# gigatron-sn76489.net
KiCad netlist of a schematic drawn in EAGLE
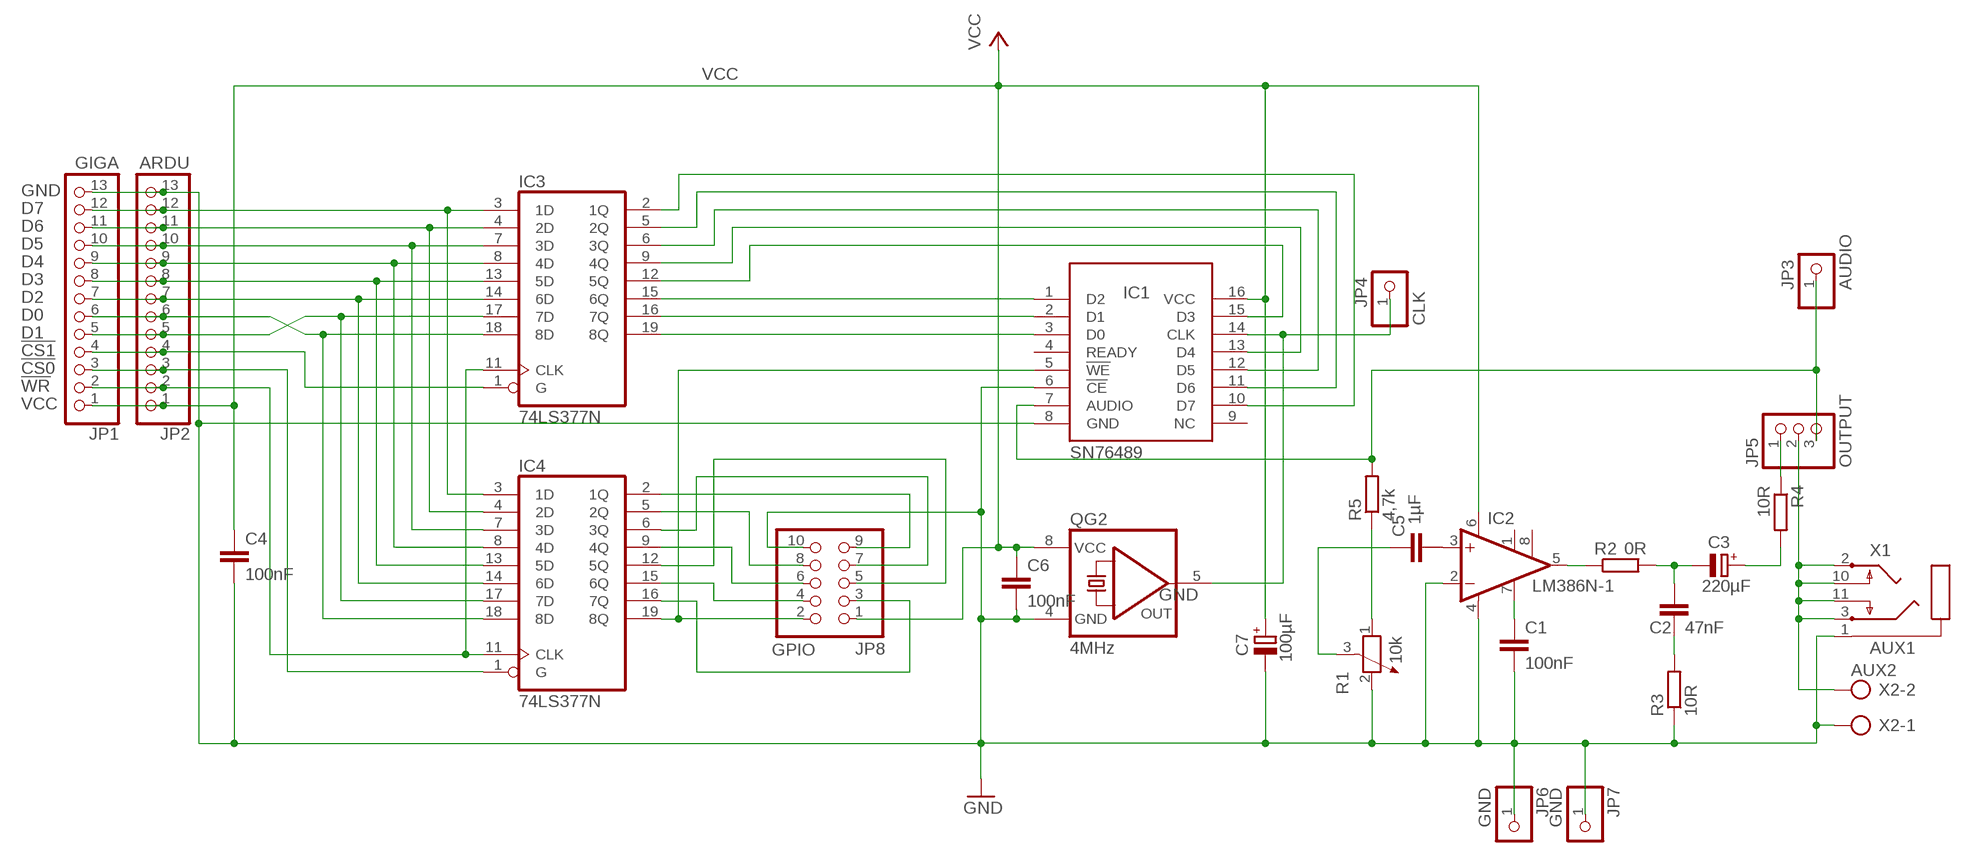
[diagram p0: schematic, sheet 1]

(export (version "E")
  (design (tool "Eeschema 10.0.6"))
  (components
    (comp (ref "C1")
      (value "100nF")
      (footprint "eagle-import:C050-025X075")
      (libsource (lib "eagle-import") (part "C-EU050-025X075"))
    )
    (comp (ref "C2")
      (value "47nF")
      (footprint "eagle-import:C050-025X075")
      (libsource (lib "eagle-import") (part "C-EU050-025X075"))
    )
    (comp (ref "C3")
      (value "220µF")
      (footprint "eagle-import:E2,5-7")
      (libsource (lib "eagle-import") (part "CPOL-EUE2.5-7"))
    )
    (comp (ref "C4")
      (value "100nF")
      (footprint "eagle-import:C050-025X075")
      (libsource (lib "eagle-import") (part "C-EU050-025X075"))
    )
    (comp (ref "C5")
      (value "1µF")
      (footprint "eagle-import:C050-025X075")
      (libsource (lib "eagle-import") (part "C-EU050-025X075"))
    )
    (comp (ref "C6")
      (value "100nF")
      (footprint "eagle-import:C050-025X075")
      (libsource (lib "eagle-import") (part "C-EU050-025X075"))
    )
    (comp (ref "C7")
      (value "100µF")
      (footprint "eagle-import:E2,5-7")
      (libsource (lib "eagle-import") (part "CPOL-EUE2.5-7"))
    )
    (comp (ref "IC1")
      (value "SN76489")
      (footprint "eagle-import:ALEX-PARTS_DIL16")
      (libsource (lib "eagle-import") (part "ALEX-PARTS_SN76489AN"))
    )
    (comp (ref "IC2")
      (value "LM386N-1")
      (footprint "eagle-import:DIL08")
      (libsource (lib "eagle-import") (part "LM386?-N1"))
    )
    (comp (ref "IC3")
      (value "74LS377N")
      (footprint "eagle-import:DIL20")
      (libsource (lib "eagle-import") (part "74377NLS"))
    )
    (comp (ref "IC4")
      (value "74LS377N")
      (footprint "eagle-import:DIL20")
      (libsource (lib "eagle-import") (part "74377NLS"))
    )
    (comp (ref "JP1")
      (value "GIGA")
      (footprint "eagle-import:1X13_90")
      (libsource (lib "eagle-import") (part "PINHD-1X13/90"))
    )
    (comp (ref "JP2")
      (value "ARDU")
      (footprint "eagle-import:1X13")
      (libsource (lib "eagle-import") (part "PINHD-1X13"))
    )
    (comp (ref "JP3")
      (value "AUDIO")
      (footprint "eagle-import:1X01")
      (libsource (lib "eagle-import") (part "PINHD-1X1"))
    )
    (comp (ref "JP4")
      (value "CLK")
      (footprint "eagle-import:1X01")
      (libsource (lib "eagle-import") (part "PINHD-1X1"))
    )
    (comp (ref "JP5")
      (value "OUTPUT")
      (footprint "eagle-import:1X03")
      (libsource (lib "eagle-import") (part "PINHD-1X3"))
    )
    (comp (ref "JP6")
      (value "GND")
      (footprint "eagle-import:1X01")
      (libsource (lib "eagle-import") (part "PINHD-1X1"))
    )
    (comp (ref "JP7")
      (value "GND")
      (footprint "eagle-import:1X01")
      (libsource (lib "eagle-import") (part "PINHD-1X1"))
    )
    (comp (ref "JP8")
      (value "GPIO")
      (footprint "eagle-import:2X05")
      (libsource (lib "eagle-import") (part "PINHD-2X5"))
    )
    (comp (ref "QG2")
      (value "4MHz")
      (footprint "eagle-import:DIL08S")
      (libsource (lib "eagle-import") (part "QG5460"))
    )
    (comp (ref "R1")
      (value "10k")
      (footprint "eagle-import:PT-10S")
      (libsource (lib "eagle-import") (part "POTENTIOMETER_PT-10S"))
    )
    (comp (ref "R2")
      (value "0R")
      (footprint "eagle-import:0207_10")
      (libsource (lib "eagle-import") (part "R-EU_0207/10"))
    )
    (comp (ref "R3")
      (value "10R")
      (footprint "eagle-import:0207_10")
      (libsource (lib "eagle-import") (part "R-EU_0207/10"))
    )
    (comp (ref "R4")
      (value "10R")
      (footprint "eagle-import:0207_10")
      (libsource (lib "eagle-import") (part "R-EU_0207/10"))
    )
    (comp (ref "R5")
      (value "4,7k")
      (footprint "eagle-import:0207_10")
      (libsource (lib "eagle-import") (part "R-EU_0207/10"))
    )
    (comp (ref "X1")
      (value "AUX1")
      (footprint "eagle-import:SJ1-352XN")
      (libsource (lib "eagle-import") (part "CON-SJ1-352XNSJ1-352XN"))
    )
    (comp (ref "X2")
      (value "AUX2")
      (footprint "eagle-import:AK500_2")
      (libsource (lib "eagle-import") (part "AK500/2"))
    )
  )
  (nets
    (net (code "1") (name "/D0") (class "Default")
      (node (ref "IC3") (pin "18") (pinfunction "8D_18") (pintype "input"))
      (node (ref "IC4") (pin "18") (pinfunction "8D_18") (pintype "input"))
      (node (ref "JP1") (pin "6") (pinfunction "6_6") (pintype "passive"))
      (node (ref "JP2") (pin "6") (pinfunction "6_6") (pintype "passive"))
    )
    (net (code "2") (name "/D1") (class "Default")
      (node (ref "IC3") (pin "17") (pinfunction "7D_17") (pintype "input"))
      (node (ref "IC4") (pin "17") (pinfunction "7D_17") (pintype "input"))
      (node (ref "JP1") (pin "5") (pinfunction "5_5") (pintype "passive"))
      (node (ref "JP2") (pin "5") (pinfunction "5_5") (pintype "passive"))
    )
    (net (code "3") (name "/D2") (class "Default")
      (node (ref "IC3") (pin "14") (pinfunction "6D_14") (pintype "input"))
      (node (ref "IC4") (pin "14") (pinfunction "6D_14") (pintype "input"))
      (node (ref "JP1") (pin "7") (pinfunction "7_7") (pintype "passive"))
      (node (ref "JP2") (pin "7") (pinfunction "7_7") (pintype "passive"))
    )
    (net (code "4") (name "/D3") (class "Default")
      (node (ref "IC3") (pin "13") (pinfunction "5D_13") (pintype "input"))
      (node (ref "IC4") (pin "13") (pinfunction "5D_13") (pintype "input"))
      (node (ref "JP1") (pin "8") (pinfunction "8_8") (pintype "passive"))
      (node (ref "JP2") (pin "8") (pinfunction "8_8") (pintype "passive"))
    )
    (net (code "5") (name "/D4") (class "Default")
      (node (ref "IC3") (pin "8") (pinfunction "4D_8") (pintype "input"))
      (node (ref "IC4") (pin "8") (pinfunction "4D_8") (pintype "input"))
      (node (ref "JP1") (pin "9") (pinfunction "9_9") (pintype "passive"))
      (node (ref "JP2") (pin "9") (pinfunction "9_9") (pintype "passive"))
    )
    (net (code "6") (name "/D5") (class "Default")
      (node (ref "IC3") (pin "7") (pinfunction "3D_7") (pintype "input"))
      (node (ref "IC4") (pin "7") (pinfunction "3D_7") (pintype "input"))
      (node (ref "JP1") (pin "10") (pinfunction "10_10") (pintype "passive"))
      (node (ref "JP2") (pin "10") (pinfunction "10_10") (pintype "passive"))
    )
    (net (code "7") (name "/D6") (class "Default")
      (node (ref "IC3") (pin "4") (pinfunction "2D_4") (pintype "input"))
      (node (ref "IC4") (pin "4") (pinfunction "2D_4") (pintype "input"))
      (node (ref "JP1") (pin "11") (pinfunction "11_11") (pintype "passive"))
      (node (ref "JP2") (pin "11") (pinfunction "11_11") (pintype "passive"))
    )
    (net (code "8") (name "/D7") (class "Default")
      (node (ref "IC3") (pin "3") (pinfunction "1D_3") (pintype "input"))
      (node (ref "IC4") (pin "3") (pinfunction "1D_3") (pintype "input"))
      (node (ref "JP1") (pin "12") (pinfunction "12_12") (pintype "passive"))
      (node (ref "JP2") (pin "12") (pinfunction "12_12") (pintype "passive"))
    )
    (net (code "9") (name "/~{CS0}") (class "Default")
      (node (ref "IC4") (pin "1") (pinfunction "G_1") (pintype "input"))
      (node (ref "JP1") (pin "3") (pinfunction "3_3") (pintype "passive"))
      (node (ref "JP2") (pin "3") (pinfunction "3_3") (pintype "passive"))
    )
    (net (code "10") (name "/~{CS1}") (class "Default")
      (node (ref "IC3") (pin "1") (pinfunction "G_1") (pintype "input"))
      (node (ref "JP1") (pin "4") (pinfunction "4_4") (pintype "passive"))
      (node (ref "JP2") (pin "4") (pinfunction "4_4") (pintype "passive"))
    )
    (net (code "11") (name "/~{WR}") (class "Default")
      (node (ref "IC3") (pin "11") (pinfunction "CLK_11") (pintype "input"))
      (node (ref "IC4") (pin "11") (pinfunction "CLK_11") (pintype "input"))
      (node (ref "JP1") (pin "2") (pinfunction "2_2") (pintype "passive"))
      (node (ref "JP2") (pin "2") (pinfunction "2_2") (pintype "passive"))
    )
    (net (code "12") (name "GND") (class "Default")
      (node (ref "C1") (pin "2") (pinfunction "2_2") (pintype "passive"))
      (node (ref "C4") (pin "2") (pinfunction "2_2") (pintype "passive"))
      (node (ref "C6") (pin "2") (pinfunction "2_2") (pintype "passive"))
      (node (ref "C7") (pin "-") (pinfunction "-_-") (pintype "passive"))
      (node (ref "IC1") (pin "6") (pinfunction "~{CE}_6") (pintype "input"))
      (node (ref "IC1") (pin "8") (pinfunction "GND_8") (pintype "power_in"))
      (node (ref "IC2") (pin "2") (pinfunction "-IN_2") (pintype "input"))
      (node (ref "IC2") (pin "4") (pinfunction "GND_4") (pintype "power_in"))
      (node (ref "JP1") (pin "13") (pinfunction "13_13") (pintype "passive"))
      (node (ref "JP2") (pin "13") (pinfunction "13_13") (pintype "passive"))
      (node (ref "JP6") (pin "1") (pinfunction "1_1") (pintype "passive"))
      (node (ref "JP7") (pin "1") (pinfunction "1_1") (pintype "passive"))
      (node (ref "JP8") (pin "10") (pinfunction "10_10") (pintype "passive"))
      (node (ref "QG2") (pin "4") (pinfunction "GND_4") (pintype "power_in"))
      (node (ref "R1") (pin "2") (pinfunction "2_2") (pintype "passive"))
      (node (ref "R3") (pin "1") (pinfunction "1_1") (pintype "passive"))
      (node (ref "X1") (pin "1") (pinfunction "1_1") (pintype "passive"))
      (node (ref "X2") (pin "1") (pinfunction "KL_1") (pintype "passive"))
    )
    (net (code "13") (name "Net-(C2-Pad1)") (class "Default")
      (node (ref "C2") (pin "1") (pinfunction "1_1") (pintype "passive"))
      (node (ref "C3") (pin "-") (pinfunction "-_-") (pintype "passive"))
      (node (ref "R2") (pin "2") (pinfunction "2_2") (pintype "passive"))
    )
    (net (code "14") (name "Net-(C2-Pad2)") (class "Default")
      (node (ref "C2") (pin "2") (pinfunction "2_2") (pintype "passive"))
      (node (ref "R3") (pin "2") (pinfunction "2_2") (pintype "passive"))
    )
    (net (code "15") (name "Net-(C3-Pad+)") (class "Default")
      (node (ref "C3") (pin "+") (pinfunction "+_+") (pintype "passive"))
      (node (ref "R4") (pin "2") (pinfunction "2_2") (pintype "passive"))
    )
    (net (code "16") (name "Net-(C5-Pad1)") (class "Default")
      (node (ref "C5") (pin "1") (pinfunction "1_1") (pintype "passive"))
      (node (ref "R1") (pin "3") (pinfunction "3_3") (pintype "passive"))
    )
    (net (code "17") (name "Net-(IC1-AUDIO)") (class "Default")
      (node (ref "IC1") (pin "7") (pinfunction "AUDIO_7") (pintype "output"))
      (node (ref "JP3") (pin "1") (pinfunction "1_1") (pintype "passive"))
      (node (ref "JP5") (pin "3") (pinfunction "3_3") (pintype "passive"))
      (node (ref "R5") (pin "2") (pinfunction "2_2") (pintype "passive"))
    )
    (net (code "18") (name "Net-(IC1-CLK)") (class "Default")
      (node (ref "IC1") (pin "14") (pinfunction "CLK_14") (pintype "input"))
      (node (ref "JP4") (pin "1") (pinfunction "1_1") (pintype "passive"))
      (node (ref "QG2") (pin "5") (pinfunction "OUT_5") (pintype "output"))
    )
    (net (code "19") (name "Net-(IC1-D0)") (class "Default")
      (node (ref "IC1") (pin "3") (pinfunction "D0_3") (pintype "input"))
      (node (ref "IC3") (pin "19") (pinfunction "8Q_19") (pintype "output"))
    )
    (net (code "20") (name "Net-(IC1-D1)") (class "Default")
      (node (ref "IC1") (pin "2") (pinfunction "D1_2") (pintype "input"))
      (node (ref "IC3") (pin "16") (pinfunction "7Q_16") (pintype "output"))
    )
    (net (code "21") (name "Net-(IC1-D2)") (class "Default")
      (node (ref "IC1") (pin "1") (pinfunction "D2_1") (pintype "input"))
      (node (ref "IC3") (pin "15") (pinfunction "6Q_15") (pintype "output"))
    )
    (net (code "22") (name "Net-(IC1-D3)") (class "Default")
      (node (ref "IC1") (pin "15") (pinfunction "D3_15") (pintype "input"))
      (node (ref "IC3") (pin "12") (pinfunction "5Q_12") (pintype "output"))
    )
    (net (code "23") (name "Net-(IC1-D4)") (class "Default")
      (node (ref "IC1") (pin "13") (pinfunction "D4_13") (pintype "input"))
      (node (ref "IC3") (pin "9") (pinfunction "4Q_9") (pintype "output"))
    )
    (net (code "24") (name "Net-(IC1-D5)") (class "Default")
      (node (ref "IC1") (pin "12") (pinfunction "D5_12") (pintype "input"))
      (node (ref "IC3") (pin "6") (pinfunction "3Q_6") (pintype "output"))
    )
    (net (code "25") (name "Net-(IC1-D6)") (class "Default")
      (node (ref "IC1") (pin "11") (pinfunction "D6_11") (pintype "input"))
      (node (ref "IC3") (pin "5") (pinfunction "2Q_5") (pintype "output"))
    )
    (net (code "26") (name "Net-(IC1-D7)") (class "Default")
      (node (ref "IC1") (pin "10") (pinfunction "D7_10") (pintype "input"))
      (node (ref "IC3") (pin "2") (pinfunction "1Q_2") (pintype "output"))
    )
    (net (code "27") (name "Net-(IC1-~{WE})") (class "Default")
      (node (ref "IC1") (pin "5") (pinfunction "~{WE}_5") (pintype "input"))
      (node (ref "IC4") (pin "19") (pinfunction "8Q_19") (pintype "output"))
      (node (ref "JP8") (pin "2") (pinfunction "2_2") (pintype "passive"))
    )
    (net (code "28") (name "Net-(IC2-+IN)") (class "Default")
      (node (ref "C5") (pin "2") (pinfunction "2_2") (pintype "passive"))
      (node (ref "IC2") (pin "3") (pinfunction "+IN_3") (pintype "input"))
    )
    (net (code "29") (name "Net-(IC2-BYPASS)") (class "Default")
      (node (ref "C1") (pin "1") (pinfunction "1_1") (pintype "passive"))
      (node (ref "IC2") (pin "7") (pinfunction "BYPASS_7") (pintype "passive"))
    )
    (net (code "30") (name "Net-(IC2-OUT)") (class "Default")
      (node (ref "IC2") (pin "5") (pinfunction "OUT_5") (pintype "output"))
      (node (ref "R2") (pin "1") (pinfunction "1_1") (pintype "passive"))
    )
    (net (code "31") (name "Net-(IC4A-1Q)") (class "Default")
      (node (ref "IC4") (pin "2") (pinfunction "1Q_2") (pintype "output"))
      (node (ref "JP8") (pin "9") (pinfunction "9_9") (pintype "passive"))
    )
    (net (code "32") (name "Net-(IC4A-2Q)") (class "Default")
      (node (ref "IC4") (pin "5") (pinfunction "2Q_5") (pintype "output"))
      (node (ref "JP8") (pin "8") (pinfunction "8_8") (pintype "passive"))
    )
    (net (code "33") (name "Net-(IC4A-3Q)") (class "Default")
      (node (ref "IC4") (pin "6") (pinfunction "3Q_6") (pintype "output"))
      (node (ref "JP8") (pin "7") (pinfunction "7_7") (pintype "passive"))
    )
    (net (code "34") (name "Net-(IC4A-4Q)") (class "Default")
      (node (ref "IC4") (pin "9") (pinfunction "4Q_9") (pintype "output"))
      (node (ref "JP8") (pin "6") (pinfunction "6_6") (pintype "passive"))
    )
    (net (code "35") (name "Net-(IC4A-5Q)") (class "Default")
      (node (ref "IC4") (pin "12") (pinfunction "5Q_12") (pintype "output"))
      (node (ref "JP8") (pin "5") (pinfunction "5_5") (pintype "passive"))
    )
    (net (code "36") (name "Net-(IC4A-6Q)") (class "Default")
      (node (ref "IC4") (pin "15") (pinfunction "6Q_15") (pintype "output"))
      (node (ref "JP8") (pin "4") (pinfunction "4_4") (pintype "passive"))
    )
    (net (code "37") (name "Net-(IC4A-7Q)") (class "Default")
      (node (ref "IC4") (pin "16") (pinfunction "7Q_16") (pintype "output"))
      (node (ref "JP8") (pin "3") (pinfunction "3_3") (pintype "passive"))
    )
    (net (code "38") (name "Net-(JP5-Pad1)") (class "Default")
      (node (ref "JP5") (pin "1") (pinfunction "1_1") (pintype "passive"))
      (node (ref "R4") (pin "1") (pinfunction "1_1") (pintype "passive"))
    )
    (net (code "39") (name "Net-(R1-Pad1)") (class "Default")
      (node (ref "R1") (pin "1") (pinfunction "1_1") (pintype "passive"))
      (node (ref "R5") (pin "1") (pinfunction "1_1") (pintype "passive"))
    )
    (net (code "40") (name "Net-(X2B-KL)") (class "Default")
      (node (ref "JP5") (pin "2") (pinfunction "2_2") (pintype "passive"))
      (node (ref "X1") (pin "10") (pinfunction "10_10") (pintype "passive"))
      (node (ref "X1") (pin "11") (pinfunction "11_11") (pintype "passive"))
      (node (ref "X1") (pin "2") (pinfunction "2_2") (pintype "passive"))
      (node (ref "X1") (pin "3") (pinfunction "3_3") (pintype "passive"))
      (node (ref "X2") (pin "2") (pinfunction "KL_2") (pintype "passive"))
    )
    (net (code "41") (name "VCC") (class "Default")
      (node (ref "C4") (pin "1") (pinfunction "1_1") (pintype "passive"))
      (node (ref "C6") (pin "1") (pinfunction "1_1") (pintype "passive"))
      (node (ref "C7") (pin "+") (pinfunction "+_+") (pintype "passive"))
      (node (ref "IC1") (pin "16") (pinfunction "VCC_16") (pintype "input"))
      (node (ref "IC2") (pin "6") (pinfunction "VS_6") (pintype "power_in"))
      (node (ref "JP1") (pin "1") (pinfunction "1_1") (pintype "passive"))
      (node (ref "JP2") (pin "1") (pinfunction "1_1") (pintype "passive"))
      (node (ref "JP8") (pin "1") (pinfunction "1_1") (pintype "passive"))
      (node (ref "QG2") (pin "8") (pinfunction "VCC_8") (pintype "power_in"))
    )
    (net (code "42") (name "unconnected-(IC1-NC-Pad9)") (class "Default")
      (node (ref "IC1") (pin "9") (pinfunction "NC_9") (pintype "no_connect"))
    )
    (net (code "43") (name "unconnected-(IC1-READY-Pad4)") (class "Default")
      (node (ref "IC1") (pin "4") (pinfunction "READY_4") (pintype "output"))
    )
    (net (code "44") (name "unconnected-(IC2-GAIN-Pad1)") (class "Default")
      (node (ref "IC2") (pin "1") (pinfunction "GAIN_1") (pintype "passive"))
    )
    (net (code "45") (name "unconnected-(IC2-GAIN-Pad8)") (class "Default")
      (node (ref "IC2") (pin "8") (pinfunction "GAIN_8") (pintype "passive"))
    )
  )
)
